# Lap_Counter.net
KiCad netlist of a schematic drawn in EAGLE
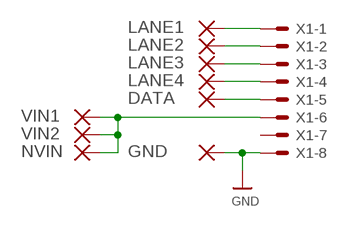
[diagram p0: schematic, sheet 1]

(export (version "E")
  (design (tool "Eeschema 10.0.6"))
  (components
    (comp (ref "DATA")
      (value "SMD5")
      (footprint "eagle-import:SMD2,54-5,08")
      (libsource (lib "eagle-import") (part "SMD5"))
    )
    (comp (ref "GND")
      (value "SMD5")
      (footprint "eagle-import:SMD2,54-5,08")
      (libsource (lib "eagle-import") (part "SMD5"))
    )
    (comp (ref "LANE1")
      (value "SMD5")
      (footprint "eagle-import:SMD2,54-5,08")
      (libsource (lib "eagle-import") (part "SMD5"))
    )
    (comp (ref "LANE2")
      (value "SMD5")
      (footprint "eagle-import:SMD2,54-5,08")
      (libsource (lib "eagle-import") (part "SMD5"))
    )
    (comp (ref "LANE3")
      (value "SMD5")
      (footprint "eagle-import:SMD2,54-5,08")
      (libsource (lib "eagle-import") (part "SMD5"))
    )
    (comp (ref "LANE4")
      (value "SMD5")
      (footprint "eagle-import:SMD2,54-5,08")
      (libsource (lib "eagle-import") (part "SMD5"))
    )
    (comp (ref "NVIN")
      (value "SMD5")
      (footprint "eagle-import:SMD2,54-5,08")
      (libsource (lib "eagle-import") (part "SMD5"))
    )
    (comp (ref "VIN1")
      (value "SMD5")
      (footprint "eagle-import:SMD2,54-5,08")
      (libsource (lib "eagle-import") (part "SMD5"))
    )
    (comp (ref "VIN2")
      (value "SMD5")
      (footprint "eagle-import:SMD2,54-5,08")
      (libsource (lib "eagle-import") (part "SMD5"))
    )
    (comp (ref "X1")
      (value "KK-156-8")
      (footprint "eagle-import:KK-156-8")
      (fields (field (name "MF") "MOLEX"))
      (libsource (lib "eagle-import") (part "KK-156-8"))
    )
  )
  (nets
    (net (code "1") (name "GND") (class "Default")
      (node (ref "GND") (pin "1") (pinfunction "P_1") (pintype "passive"))
      (node (ref "X1") (pin "8") (pinfunction "S_8") (pintype "passive"))
    )
    (net (code "2") (name "Net-(DATA-P)") (class "Default")
      (node (ref "DATA") (pin "1") (pinfunction "P_1") (pintype "passive"))
      (node (ref "X1") (pin "5") (pinfunction "S_5") (pintype "passive"))
    )
    (net (code "3") (name "Net-(LANE1-P)") (class "Default")
      (node (ref "LANE1") (pin "1") (pinfunction "P_1") (pintype "passive"))
      (node (ref "X1") (pin "1") (pinfunction "S_1") (pintype "passive"))
    )
    (net (code "4") (name "Net-(LANE2-P)") (class "Default")
      (node (ref "LANE2") (pin "1") (pinfunction "P_1") (pintype "passive"))
      (node (ref "X1") (pin "2") (pinfunction "S_2") (pintype "passive"))
    )
    (net (code "5") (name "Net-(LANE3-P)") (class "Default")
      (node (ref "LANE3") (pin "1") (pinfunction "P_1") (pintype "passive"))
      (node (ref "X1") (pin "3") (pinfunction "S_3") (pintype "passive"))
    )
    (net (code "6") (name "Net-(LANE4-P)") (class "Default")
      (node (ref "LANE4") (pin "1") (pinfunction "P_1") (pintype "passive"))
      (node (ref "X1") (pin "4") (pinfunction "S_4") (pintype "passive"))
    )
    (net (code "7") (name "Net-(NVIN-P)") (class "Default")
      (node (ref "NVIN") (pin "1") (pinfunction "P_1") (pintype "passive"))
      (node (ref "VIN1") (pin "1") (pinfunction "P_1") (pintype "passive"))
      (node (ref "VIN2") (pin "1") (pinfunction "P_1") (pintype "passive"))
      (node (ref "X1") (pin "6") (pinfunction "S_6") (pintype "passive"))
    )
    (net (code "8") (name "unconnected-(X1G-S-Pad7)") (class "Default")
      (node (ref "X1") (pin "7") (pinfunction "S_7") (pintype "passive"))
    )
  )
)
